# v0_2.net
KiCad netlist of a schematic drawn in EAGLE
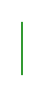
[diagram p0: schematic, sheet 1, part 1 of 2]
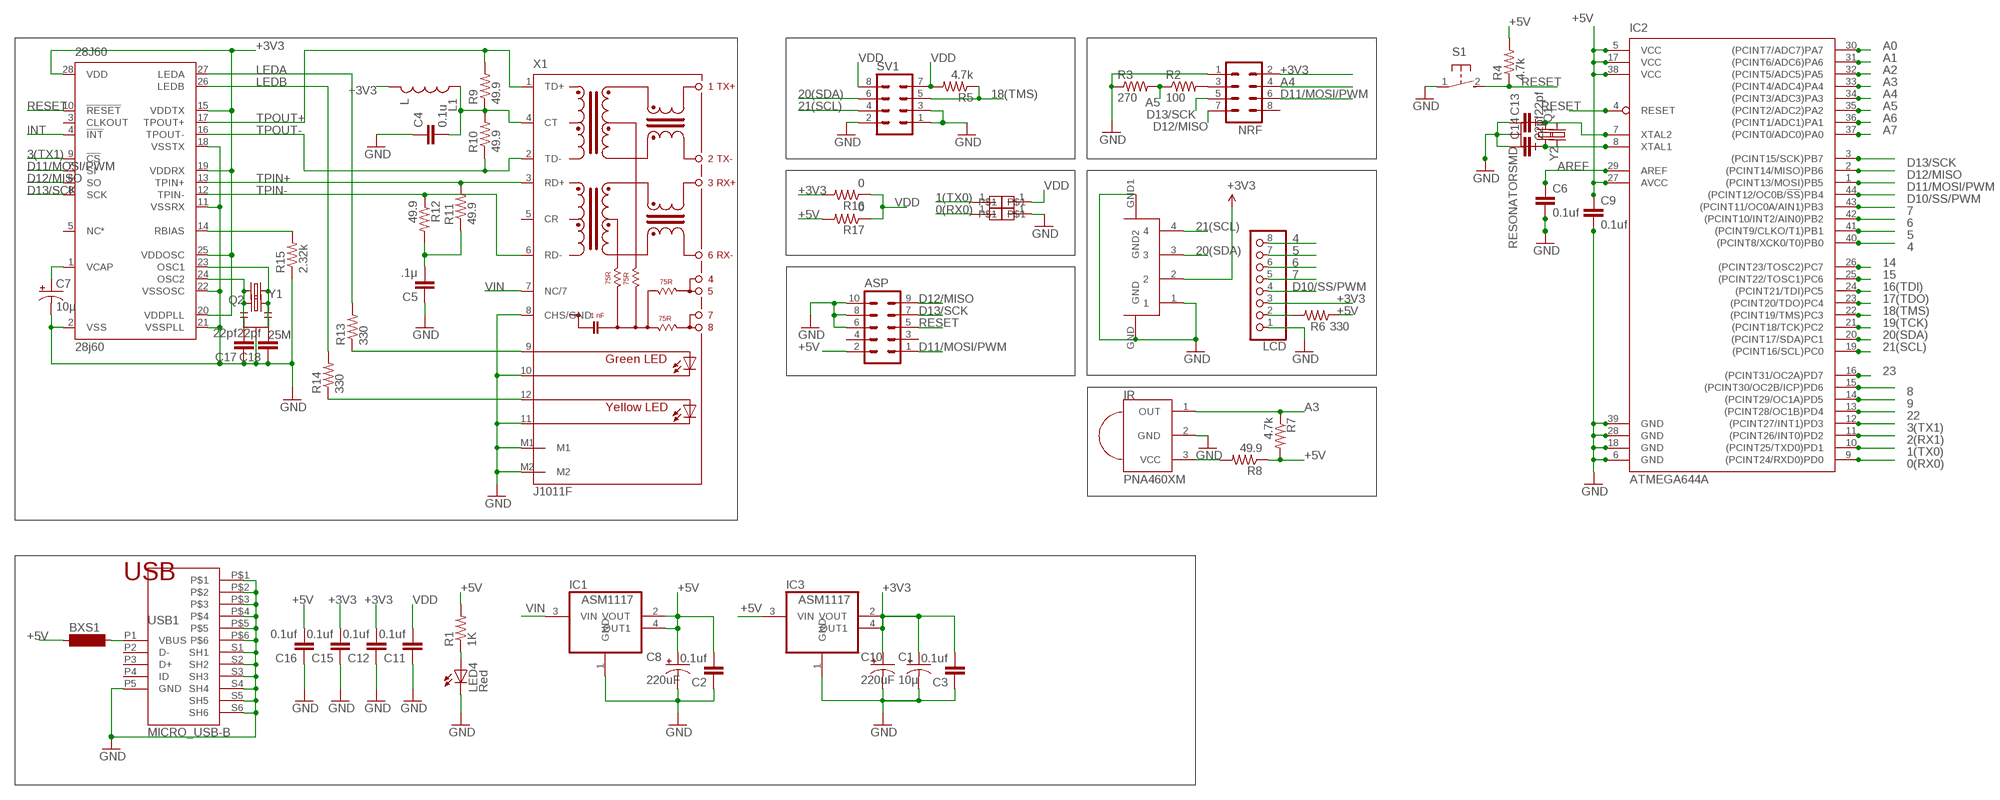
[diagram p1: schematic, sheet 1, part 2 of 2]

(export (version "E")
  (design (tool "Eeschema 10.0.6"))
  (components
    (comp (ref "28J60")
      (value "28j60")
      (footprint "eagle-import:SSOP28DB")
      (libsource (lib "eagle-import") (part "ENC28J60/SS"))
    )
    (comp (ref "ASP")
      (value "MA05-2")
      (footprint "eagle-import:MA05-2")
      (libsource (lib "eagle-import") (part "MA05-2"))
    )
    (comp (ref "BXS1")
      (value "SM-1206")
      (footprint "eagle-import:SM-1206")
      (fields (field (name "OC_FARNELL") "unknown") (field (name "OC_NEWARK") "unknown"))
      (libsource (lib "eagle-import") (part "SM-1206"))
    )
    (comp (ref "C1")
      (value "10μ")
      (footprint "eagle-import:EIA3528")
      (libsource (lib "eagle-import") (part "CAP_POL3528"))
    )
    (comp (ref "C2")
      (value "0.1uf")
      (footprint "eagle-import:0603-CAP")
      (libsource (lib "eagle-import") (part "MY_CAP0603-CAP"))
    )
    (comp (ref "C3")
      (value "0.1uf")
      (footprint "eagle-import:0603-CAP")
      (libsource (lib "eagle-import") (part "MY_CAP0603-CAP"))
    )
    (comp (ref "C4")
      (value "0.1u")
      (footprint "eagle-import:0603-CAP")
      (libsource (lib "eagle-import") (part "CAP0603-CAP"))
    )
    (comp (ref "C5")
      (value ".1μ")
      (footprint "eagle-import:0603-CAP")
      (libsource (lib "eagle-import") (part "CAP0603-CAP"))
    )
    (comp (ref "C6")
      (value "0.1uf")
      (footprint "eagle-import:0603-CAP")
      (libsource (lib "eagle-import") (part "CAP0603-CAP"))
    )
    (comp (ref "C7")
      (value "10μ")
      (footprint "eagle-import:EIA3528")
      (libsource (lib "eagle-import") (part "CAP_POL3528"))
    )
    (comp (ref "C8")
      (value "220uF")
      (footprint "eagle-import:153CLV-0605")
      (libsource (lib "eagle-import") (part "CPOL-US153CLV-0605"))
    )
    (comp (ref "C9")
      (value "0.1uf")
      (footprint "eagle-import:0603-CAP")
      (libsource (lib "eagle-import") (part "CAP0603-CAP"))
    )
    (comp (ref "C10")
      (value "220uF")
      (footprint "eagle-import:153CLV-0605")
      (libsource (lib "eagle-import") (part "CPOL-US153CLV-0605"))
    )
    (comp (ref "C11")
      (value "0.1uf")
      (footprint "eagle-import:0603-CAP")
      (libsource (lib "eagle-import") (part "MY_CAP0603-CAP"))
    )
    (comp (ref "C12")
      (value "0.1uf")
      (footprint "eagle-import:0603-CAP")
      (libsource (lib "eagle-import") (part "MY_CAP0603-CAP"))
    )
    (comp (ref "C13")
      (value "22pf")
      (footprint "eagle-import:0603-CAP")
      (libsource (lib "eagle-import") (part "CAP0603-CAP"))
    )
    (comp (ref "C14")
      (value "22pf")
      (footprint "eagle-import:0603-CAP")
      (libsource (lib "eagle-import") (part "CAP0603-CAP"))
    )
    (comp (ref "C15")
      (value "0.1uf")
      (footprint "eagle-import:0603-CAP")
      (libsource (lib "eagle-import") (part "MY_CAP0603-CAP"))
    )
    (comp (ref "C16")
      (value "0.1uf")
      (footprint "eagle-import:0603-CAP")
      (libsource (lib "eagle-import") (part "MY_CAP0603-CAP"))
    )
    (comp (ref "C17")
      (value "22pf")
      (footprint "eagle-import:0603-CAP")
      (libsource (lib "eagle-import") (part "CAP0603-CAP"))
    )
    (comp (ref "C18")
      (value "22pf")
      (footprint "eagle-import:0603-CAP")
      (libsource (lib "eagle-import") (part "CAP0603-CAP"))
    )
    (comp (ref "IC1")
      (value "ASM1117")
      (footprint "eagle-import:SOT223")
      (fields (field (name "MPN") "REG1117"))
      (libsource (lib "eagle-import") (part "ASM1117"))
    )
    (comp (ref "IC2")
      (value "ATMEGA644A")
      (footprint "eagle-import:TQFP44")
      (fields (field (name "MPN") "ATMEGA644PV-10AU"))
      (libsource (lib "eagle-import") (part "ATMEGA644A"))
    )
    (comp (ref "IC3")
      (value "ASM1117")
      (footprint "eagle-import:SOT223")
      (fields
        (field (name "MPN") "REG1117")
        (field (name "MPN_1") "REG1117")
        (field (name "OC_FARNELL") "1097566")
        (field (name "OC_NEWARK") "14P6981")
      )
      (libsource (lib "eagle-import") (part "ASM1117"))
    )
    (comp (ref "IR")
      (value "PNA460XM")
      (footprint "eagle-import:PNA460XM")
      (libsource (lib "eagle-import") (part "PNA460XM"))
    )
    (comp (ref "L1")
      (value "L")
      (footprint "eagle-import:0603")
      (libsource (lib "eagle-import") (part "INDUCTOR0603"))
    )
    (comp (ref "LCD")
      (value "PINHD-1X8")
      (footprint "eagle-import:1X08")
      (libsource (lib "eagle-import") (part "PINHD-1X8"))
    )
    (comp (ref "LED4")
      (value "Red")
      (footprint "eagle-import:0805-LED")
      (libsource (lib "eagle-import") (part "LED0805"))
    )
    (comp (ref "NRF")
      (value "MA04-2")
      (footprint "eagle-import:MA04-2")
      (libsource (lib "eagle-import") (part "MA04-2"))
    )
    (comp (ref "Q1")
      (value "CRYSTALHC49S")
      (footprint "eagle-import:HC49_S")
      (libsource (lib "eagle-import") (part "CRYSTALHC49S"))
    )
    (comp (ref "Q2")
      (value "CRYSTALHC49S")
      (footprint "eagle-import:HC49_S")
      (fields (field (name "OC_FARNELL") "1667008") (field (name "OC_NEWARK") "unknown"))
      (libsource (lib "eagle-import") (part "CRYSTALHC49S"))
    )
    (comp (ref "R1")
      (value "1K")
      (footprint "eagle-import:0603-RES")
      (libsource (lib "eagle-import") (part "MY_RESISTOR0603-RES"))
    )
    (comp (ref "R2")
      (value "100")
      (footprint "eagle-import:0603-RES")
      (libsource (lib "eagle-import") (part "MY_RESISTOR0603-RES"))
    )
    (comp (ref "R3")
      (value "270")
      (footprint "eagle-import:0603-RES")
      (libsource (lib "eagle-import") (part "MY_RESISTOR0603-RES"))
    )
    (comp (ref "R4")
      (value "4.7k")
      (footprint "eagle-import:0603-RES")
      (libsource (lib "eagle-import") (part "RESISTOR0603-RES"))
    )
    (comp (ref "R5")
      (value "4.7k")
      (footprint "eagle-import:0603-RES")
      (libsource (lib "eagle-import") (part "MY_RESISTOR0603-RES"))
    )
    (comp (ref "R6")
      (value "330")
      (footprint "eagle-import:0603-RES")
      (libsource (lib "eagle-import") (part "MY_RESISTOR0603-RES"))
    )
    (comp (ref "R7")
      (value "4.7k")
      (footprint "eagle-import:0603-RES")
      (libsource (lib "eagle-import") (part "MY_RESISTOR0603-RES"))
    )
    (comp (ref "R8")
      (value "49.9")
      (footprint "eagle-import:0603-RES")
      (libsource (lib "eagle-import") (part "MY_RESISTOR0603-RES"))
    )
    (comp (ref "R9")
      (value "49.9")
      (footprint "eagle-import:0603-RES")
      (libsource (lib "eagle-import") (part "RESISTOR0603-RES"))
    )
    (comp (ref "R10")
      (value "49.9")
      (footprint "eagle-import:0603-RES")
      (libsource (lib "eagle-import") (part "RESISTOR0603-RES"))
    )
    (comp (ref "R11")
      (value "49.9")
      (footprint "eagle-import:0603-RES")
      (libsource (lib "eagle-import") (part "RESISTOR0603-RES"))
    )
    (comp (ref "R12")
      (value "49.9")
      (footprint "eagle-import:0603-RES")
      (libsource (lib "eagle-import") (part "RESISTOR0603-RES"))
    )
    (comp (ref "R13")
      (value "330")
      (footprint "eagle-import:0603-RES")
      (libsource (lib "eagle-import") (part "RESISTOR0603-RES"))
    )
    (comp (ref "R14")
      (value "330")
      (footprint "eagle-import:0603-RES")
      (libsource (lib "eagle-import") (part "RESISTOR0603-RES"))
    )
    (comp (ref "R15")
      (value "2.32k")
      (footprint "eagle-import:0603-RES")
      (libsource (lib "eagle-import") (part "RESISTOR0603-RES"))
    )
    (comp (ref "R16")
      (value "0")
      (footprint "eagle-import:0603-RES")
      (libsource (lib "eagle-import") (part "MY_RESISTOR0603-RES"))
    )
    (comp (ref "R17")
      (value "0")
      (footprint "eagle-import:0603-RES")
      (libsource (lib "eagle-import") (part "MY_RESISTOR0603-RES"))
    )
    (comp (ref "S1")
      (value "31-XX")
      (footprint "eagle-import:B3F-31XX")
      (fields (field (name "MPN") "B3F-3100"))
      (libsource (lib "eagle-import") (part "31-XX"))
    )
    (comp (ref "SV1")
      (value "MA04-2")
      (footprint "eagle-import:MA04-2")
      (libsource (lib "eagle-import") (part "MA04-2"))
    )
    (comp (ref "U$2")
      (value "S4B-XH-SM4-TB")
      (footprint "eagle-import:XH-SM4-TB")
      (libsource (lib "eagle-import") (part "S4B-XH-SM4-TB"))
    )
    (comp (ref "U$4")
      (value "PIN1")
      (footprint "eagle-import:PIN1")
      (libsource (lib "eagle-import") (part "PIN1"))
    )
    (comp (ref "U$5")
      (value "PIN1")
      (footprint "eagle-import:PIN1")
      (libsource (lib "eagle-import") (part "PIN1"))
    )
    (comp (ref "U$6")
      (value "PIN1")
      (footprint "eagle-import:PIN1")
      (libsource (lib "eagle-import") (part "PIN1"))
    )
    (comp (ref "U$7")
      (value "PIN1")
      (footprint "eagle-import:PIN1")
      (libsource (lib "eagle-import") (part "PIN1"))
    )
    (comp (ref "USB1")
      (value "MICRO_USB-B")
      (footprint "eagle-import:USB_MICRO_B")
      (libsource (lib "eagle-import") (part "MICRO_USB-B"))
    )
    (comp (ref "X1")
      (value "J1011F")
      (footprint "eagle-import:HRJ")
      (libsource (lib "eagle-import") (part "RJ45-HR911105A"))
    )
    (comp (ref "Y1")
      (value "25M")
      (footprint "eagle-import:RESONATOR-SMD")
      (libsource (lib "eagle-import") (part "RESONATORSMD"))
    )
    (comp (ref "Y2")
      (value "RESONATORSMD")
      (footprint "eagle-import:RESONATOR-SMD")
      (libsource (lib "eagle-import") (part "MY_RESONATORSMD"))
    )
  )
  (nets
    (net (code "1") (name "+3V3") (class "Default")
      (node (ref "28J60") (pin "15") (pinfunction "VDDTX_15") (pintype "input"))
      (node (ref "28J60") (pin "19") (pinfunction "VDDRX_19") (pintype "input"))
      (node (ref "28J60") (pin "20") (pinfunction "VDDPLL_20") (pintype "input"))
      (node (ref "28J60") (pin "25") (pinfunction "VDDOSC_25") (pintype "input"))
      (node (ref "28J60") (pin "28") (pinfunction "VDD_28") (pintype "input"))
      (node (ref "C1") (pin "A") (pinfunction "+_A") (pintype "passive"))
      (node (ref "C10") (pin "+") (pinfunction "+_+") (pintype "passive"))
      (node (ref "C12") (pin "2") (pinfunction "2_2") (pintype "passive"))
      (node (ref "C15") (pin "2") (pinfunction "2_2") (pintype "passive"))
      (node (ref "C3") (pin "2") (pinfunction "2_2") (pintype "passive"))
      (node (ref "IC3") (pin "2") (pinfunction "VOUT_2") (pintype "output"))
      (node (ref "IC3") (pin "4") (pinfunction "OUT1_4") (pintype "bidirectional"))
      (node (ref "L1") (pin "2") (pinfunction "2_2") (pintype "passive"))
      (node (ref "LCD") (pin "3") (pinfunction "3_3") (pintype "passive"))
      (node (ref "NRF") (pin "2") (pinfunction "2_2") (pintype "passive"))
      (node (ref "R16") (pin "2") (pinfunction "2_2") (pintype "passive"))
      (node (ref "U$2") (pin "2") (pinfunction "2_2") (pintype "bidirectional"))
    )
    (net (code "2") (name "/+5V") (class "Default")
      (node (ref "ASP") (pin "2") (pinfunction "2_2") (pintype "passive"))
      (node (ref "BXS1") (pin "1") (pinfunction "1_1") (pintype "passive"))
      (node (ref "C16") (pin "2") (pinfunction "2_2") (pintype "passive"))
      (node (ref "C2") (pin "2") (pinfunction "2_2") (pintype "passive"))
      (node (ref "C8") (pin "+") (pinfunction "+_+") (pintype "passive"))
      (node (ref "C9") (pin "1") (pinfunction "1_1") (pintype "passive"))
      (node (ref "IC1") (pin "2") (pinfunction "VOUT_2") (pintype "output"))
      (node (ref "IC1") (pin "4") (pinfunction "OUT1_4") (pintype "bidirectional"))
      (node (ref "IC2") (pin "17") (pinfunction "VCC_17") (pintype "power_in"))
      (node (ref "IC2") (pin "27") (pinfunction "AVCC_27") (pintype "power_in"))
      (node (ref "IC2") (pin "38") (pinfunction "VCC_38") (pintype "power_in"))
      (node (ref "IC2") (pin "5") (pinfunction "VCC_5") (pintype "power_in"))
      (node (ref "IC3") (pin "3") (pinfunction "VIN_3") (pintype "input"))
      (node (ref "R1") (pin "2") (pinfunction "2_2") (pintype "passive"))
      (node (ref "R17") (pin "2") (pinfunction "2_2") (pintype "passive"))
      (node (ref "R4") (pin "2") (pinfunction "2_2") (pintype "passive"))
      (node (ref "R6") (pin "1") (pinfunction "1_1") (pintype "passive"))
      (node (ref "R7") (pin "2") (pinfunction "2_2") (pintype "passive"))
      (node (ref "R8") (pin "1") (pinfunction "1_1") (pintype "passive"))
    )
    (net (code "3") (name "/0(RX0)") (class "Default")
      (node (ref "IC2") (pin "9") (pinfunction "(PCINT24/RXD0)PD0_9") (pintype "bidirectional"))
      (node (ref "U$7") (pin "1") (pinfunction "P$1_1") (pintype "bidirectional"))
    )
    (net (code "4") (name "/1(TX0)") (class "Default")
      (node (ref "IC2") (pin "10") (pinfunction "(PCINT25/TXD0)PD1_10") (pintype "bidirectional"))
      (node (ref "U$6") (pin "1") (pinfunction "P$1_1") (pintype "bidirectional"))
    )
    (net (code "5") (name "/2(RX1)") (class "Default")
      (node (ref "IC2") (pin "11") (pinfunction "(PCINT26/INT0)PD2_11") (pintype "bidirectional"))
    )
    (net (code "6") (name "/3(TX1)") (class "Default")
      (node (ref "28J60") (pin "9") (pinfunction "~{CS}_9") (pintype "input"))
      (node (ref "IC2") (pin "12") (pinfunction "(PCINT27/INT1)PD3_12") (pintype "bidirectional"))
    )
    (net (code "7") (name "/4") (class "Default")
      (node (ref "IC2") (pin "40") (pinfunction "(PCINT8/XCK0/T0)PB0_40") (pintype "bidirectional"))
      (node (ref "LCD") (pin "8") (pinfunction "8_8") (pintype "passive"))
    )
    (net (code "8") (name "/5") (class "Default")
      (node (ref "IC2") (pin "41") (pinfunction "(PCINT9/CLKO/T1)PB1_41") (pintype "bidirectional"))
      (node (ref "LCD") (pin "7") (pinfunction "7_7") (pintype "passive"))
    )
    (net (code "9") (name "/6") (class "Default")
      (node (ref "IC2") (pin "42") (pinfunction "(PCINT10/INT2/AIN0)PB2_42") (pintype "bidirectional"))
      (node (ref "LCD") (pin "6") (pinfunction "6_6") (pintype "passive"))
    )
    (net (code "10") (name "/7") (class "Default")
      (node (ref "IC2") (pin "43") (pinfunction "(PCINT11/OC0A/AIN1)PB3_43") (pintype "bidirectional"))
      (node (ref "LCD") (pin "5") (pinfunction "5_5") (pintype "passive"))
    )
    (net (code "11") (name "/8") (class "Default")
      (node (ref "IC2") (pin "15") (pinfunction "(PCINT30/OC2B/ICP)PD6_15") (pintype "bidirectional"))
    )
    (net (code "12") (name "/9") (class "Default")
      (node (ref "IC2") (pin "14") (pinfunction "(PCINT29/OC1A)PD5_14") (pintype "bidirectional"))
    )
    (net (code "13") (name "/14") (class "Default")
      (node (ref "IC2") (pin "26") (pinfunction "(PCINT23/TOSC2)PC7_26") (pintype "output"))
    )
    (net (code "14") (name "/15") (class "Default")
      (node (ref "IC2") (pin "25") (pinfunction "(PCINT22/TOSC1)PC6_25") (pintype "output"))
    )
    (net (code "15") (name "/16(TDI)") (class "Default")
      (node (ref "IC2") (pin "24") (pinfunction "(PCINT21/TDI)PC5_24") (pintype "output"))
    )
    (net (code "16") (name "/17(TDO)") (class "Default")
      (node (ref "IC2") (pin "23") (pinfunction "(PCINT20/TDO)PC4_23") (pintype "output"))
    )
    (net (code "17") (name "/18(TMS)") (class "Default")
      (node (ref "IC2") (pin "22") (pinfunction "(PCINT19/TMS)PC3_22") (pintype "output"))
      (node (ref "R5") (pin "1") (pinfunction "1_1") (pintype "passive"))
      (node (ref "SV1") (pin "5") (pinfunction "5_5") (pintype "passive"))
    )
    (net (code "18") (name "/19(TCK)") (class "Default")
      (node (ref "IC2") (pin "21") (pinfunction "(PCINT18/TCK)PC2_21") (pintype "output"))
    )
    (net (code "19") (name "/20(SDA)") (class "Default")
      (node (ref "IC2") (pin "20") (pinfunction "(PCINT17/SDA)PC1_20") (pintype "output"))
      (node (ref "SV1") (pin "6") (pinfunction "6_6") (pintype "passive"))
      (node (ref "U$2") (pin "3") (pinfunction "3_3") (pintype "bidirectional"))
    )
    (net (code "20") (name "/21(SCL)") (class "Default")
      (node (ref "IC2") (pin "19") (pinfunction "(PCINT16/SCL)PC0_19") (pintype "output"))
      (node (ref "SV1") (pin "4") (pinfunction "4_4") (pintype "passive"))
      (node (ref "U$2") (pin "4") (pinfunction "4_4") (pintype "bidirectional"))
    )
    (net (code "21") (name "/22") (class "Default")
      (node (ref "IC2") (pin "13") (pinfunction "(PCINT28/OC1B)PD4_13") (pintype "bidirectional"))
    )
    (net (code "22") (name "/23") (class "Default")
      (node (ref "IC2") (pin "16") (pinfunction "(PCINT31/OC2A)PD7_16") (pintype "bidirectional"))
    )
    (net (code "23") (name "/A0") (class "Default")
      (node (ref "IC2") (pin "30") (pinfunction "(PCINT7/ADC7)PA7_30") (pintype "bidirectional"))
    )
    (net (code "24") (name "/A1") (class "Default")
      (node (ref "IC2") (pin "31") (pinfunction "(PCINT6/ADC6)PA6_31") (pintype "bidirectional"))
    )
    (net (code "25") (name "/A2") (class "Default")
      (node (ref "IC2") (pin "32") (pinfunction "(PCINT5/ADC5)PA5_32") (pintype "bidirectional"))
    )
    (net (code "26") (name "/A3") (class "Default")
      (node (ref "IC2") (pin "33") (pinfunction "(PCINT4/ADC4)PA4_33") (pintype "bidirectional"))
      (node (ref "IR") (pin "1") (pinfunction "OUT_1") (pintype "output"))
      (node (ref "R7") (pin "1") (pinfunction "1_1") (pintype "passive"))
    )
    (net (code "27") (name "/A4") (class "Default")
      (node (ref "IC2") (pin "34") (pinfunction "(PCINT3/ADC3)PA3_34") (pintype "bidirectional"))
      (node (ref "NRF") (pin "4") (pinfunction "4_4") (pintype "passive"))
    )
    (net (code "28") (name "/A5") (class "Default")
      (node (ref "IC2") (pin "35") (pinfunction "(PCINT2/ADC2)PA2_35") (pintype "bidirectional"))
      (node (ref "R2") (pin "1") (pinfunction "1_1") (pintype "passive"))
      (node (ref "R3") (pin "2") (pinfunction "2_2") (pintype "passive"))
    )
    (net (code "29") (name "/A6") (class "Default")
      (node (ref "IC2") (pin "36") (pinfunction "(PCINT1/ADC1)PA1_36") (pintype "bidirectional"))
    )
    (net (code "30") (name "/A7") (class "Default")
      (node (ref "IC2") (pin "37") (pinfunction "(PCINT0/ADC0)PA0_37") (pintype "bidirectional"))
    )
    (net (code "31") (name "/AREF") (class "Default")
      (node (ref "C6") (pin "1") (pinfunction "1_1") (pintype "passive"))
      (node (ref "IC2") (pin "29") (pinfunction "AREF_29") (pintype "passive"))
    )
    (net (code "32") (name "/D10{slash}SS{slash}PWM") (class "Default")
      (node (ref "IC2") (pin "44") (pinfunction "(PCINT12/OC0B/~{SS})PB4_44") (pintype "bidirectional"))
      (node (ref "LCD") (pin "4") (pinfunction "4_4") (pintype "passive"))
    )
    (net (code "33") (name "/D11{slash}MOSI{slash}PWM") (class "Default")
      (node (ref "28J60") (pin "7") (pinfunction "SI_7") (pintype "input"))
      (node (ref "ASP") (pin "1") (pinfunction "1_1") (pintype "passive"))
      (node (ref "IC2") (pin "1") (pinfunction "(PCINT13/MOSI)PB5_1") (pintype "bidirectional"))
      (node (ref "NRF") (pin "6") (pinfunction "6_6") (pintype "passive"))
    )
    (net (code "34") (name "/D12{slash}MISO") (class "Default")
      (node (ref "28J60") (pin "6") (pinfunction "SO_6") (pintype "output"))
      (node (ref "ASP") (pin "9") (pinfunction "9_9") (pintype "passive"))
      (node (ref "IC2") (pin "2") (pinfunction "(PCINT14/MISO)PB6_2") (pintype "bidirectional"))
      (node (ref "NRF") (pin "7") (pinfunction "7_7") (pintype "passive"))
    )
    (net (code "35") (name "/D13{slash}SCK") (class "Default")
      (node (ref "28J60") (pin "8") (pinfunction "SCK_8") (pintype "input"))
      (node (ref "ASP") (pin "7") (pinfunction "7_7") (pintype "passive"))
      (node (ref "IC2") (pin "3") (pinfunction "(PCINT15/SCK)PB7_3") (pintype "bidirectional"))
      (node (ref "NRF") (pin "5") (pinfunction "5_5") (pintype "passive"))
    )
    (net (code "36") (name "/INT") (class "Default")
      (node (ref "28J60") (pin "4") (pinfunction "~{INT}_4") (pintype "output"))
    )
    (net (code "37") (name "/LEDA") (class "Default")
      (node (ref "28J60") (pin "27") (pinfunction "LEDA_27") (pintype "output"))
      (node (ref "R13") (pin "2") (pinfunction "2_2") (pintype "passive"))
    )
    (net (code "38") (name "/LEDB") (class "Default")
      (node (ref "28J60") (pin "26") (pinfunction "LEDB_26") (pintype "output"))
      (node (ref "R14") (pin "2") (pinfunction "2_2") (pintype "passive"))
    )
    (net (code "39") (name "/RESET") (class "Default")
      (node (ref "28J60") (pin "10") (pinfunction "~{RESET}_10") (pintype "input"))
      (node (ref "ASP") (pin "5") (pinfunction "5_5") (pintype "passive"))
      (node (ref "IC2") (pin "4") (pinfunction "RESET_4") (pintype "input"))
      (node (ref "R4") (pin "1") (pinfunction "1_1") (pintype "passive"))
      (node (ref "S1") (pin "2") (pinfunction "S_2") (pintype "passive"))
    )
    (net (code "40") (name "/TPIN+") (class "Default")
      (node (ref "28J60") (pin "13") (pinfunction "TPIN+_13") (pintype "input"))
      (node (ref "R11") (pin "2") (pinfunction "2_2") (pintype "passive"))
      (node (ref "X1") (pin "3") (pinfunction "RD+_3") (pintype "input"))
    )
    (net (code "41") (name "/TPIN-") (class "Default")
      (node (ref "28J60") (pin "12") (pinfunction "TPIN-_12") (pintype "input"))
      (node (ref "R12") (pin "1") (pinfunction "1_1") (pintype "passive"))
      (node (ref "X1") (pin "6") (pinfunction "RD-_6") (pintype "input"))
    )
    (net (code "42") (name "/TPOUT+") (class "Default")
      (node (ref "28J60") (pin "17") (pinfunction "TPOUT+_17") (pintype "output"))
      (node (ref "R9") (pin "2") (pinfunction "2_2") (pintype "passive"))
      (node (ref "X1") (pin "1") (pinfunction "TD+_1") (pintype "input"))
    )
    (net (code "43") (name "/TPOUT-") (class "Default")
      (node (ref "28J60") (pin "16") (pinfunction "TPOUT-_16") (pintype "output"))
      (node (ref "R10") (pin "1") (pinfunction "1_1") (pintype "passive"))
      (node (ref "X1") (pin "2") (pinfunction "TD-_2") (pintype "input"))
    )
    (net (code "44") (name "/VDD") (class "Default")
      (node (ref "C11") (pin "2") (pinfunction "2_2") (pintype "passive"))
      (node (ref "R16") (pin "1") (pinfunction "1_1") (pintype "passive"))
      (node (ref "R17") (pin "1") (pinfunction "1_1") (pintype "passive"))
      (node (ref "R5") (pin "2") (pinfunction "2_2") (pintype "passive"))
      (node (ref "SV1") (pin "7") (pinfunction "7_7") (pintype "passive"))
      (node (ref "SV1") (pin "8") (pinfunction "8_8") (pintype "passive"))
      (node (ref "U$5") (pin "1") (pinfunction "P$1_1") (pintype "bidirectional"))
    )
    (net (code "45") (name "/VIN") (class "Default")
      (node (ref "IC1") (pin "3") (pinfunction "VIN_3") (pintype "input"))
      (node (ref "X1") (pin "7") (pinfunction "NC/7_7") (pintype "input"))
    )
    (net (code "46") (name "GND") (class "Default")
      (node (ref "28J60") (pin "11") (pinfunction "VSSRX_11") (pintype "input"))
      (node (ref "28J60") (pin "18") (pinfunction "VSSTX_18") (pintype "input"))
      (node (ref "28J60") (pin "2") (pinfunction "VSS_2") (pintype "input"))
      (node (ref "28J60") (pin "21") (pinfunction "VSSPLL_21") (pintype "input"))
      (node (ref "28J60") (pin "22") (pinfunction "VSSOSC_22") (pintype "input"))
      (node (ref "ASP") (pin "10") (pinfunction "10_10") (pintype "passive"))
      (node (ref "ASP") (pin "6") (pinfunction "6_6") (pintype "passive"))
      (node (ref "ASP") (pin "8") (pinfunction "8_8") (pintype "passive"))
      (node (ref "C1") (pin "C") (pinfunction "-_C") (pintype "passive"))
      (node (ref "C10") (pin "-") (pinfunction "-_-") (pintype "passive"))
      (node (ref "C11") (pin "1") (pinfunction "1_1") (pintype "passive"))
      (node (ref "C12") (pin "1") (pinfunction "1_1") (pintype "passive"))
      (node (ref "C13") (pin "1") (pinfunction "1_1") (pintype "passive"))
      (node (ref "C14") (pin "1") (pinfunction "1_1") (pintype "passive"))
      (node (ref "C15") (pin "1") (pinfunction "1_1") (pintype "passive"))
      (node (ref "C16") (pin "1") (pinfunction "1_1") (pintype "passive"))
      (node (ref "C17") (pin "1") (pinfunction "1_1") (pintype "passive"))
      (node (ref "C18") (pin "1") (pinfunction "1_1") (pintype "passive"))
      (node (ref "C2") (pin "1") (pinfunction "1_1") (pintype "passive"))
      (node (ref "C3") (pin "1") (pinfunction "1_1") (pintype "passive"))
      (node (ref "C4") (pin "1") (pinfunction "1_1") (pintype "passive"))
      (node (ref "C5") (pin "1") (pinfunction "1_1") (pintype "passive"))
      (node (ref "C6") (pin "2") (pinfunction "2_2") (pintype "passive"))
      (node (ref "C7") (pin "C") (pinfunction "-_C") (pintype "passive"))
      (node (ref "C8") (pin "-") (pinfunction "-_-") (pintype "passive"))
      (node (ref "C9") (pin "2") (pinfunction "2_2") (pintype "passive"))
      (node (ref "IC1") (pin "1") (pinfunction "GND_1") (pintype "power_in"))
      (node (ref "IC2") (pin "18") (pinfunction "GND_18") (pintype "power_in"))
      (node (ref "IC2") (pin "28") (pinfunction "GND_28") (pintype "power_in"))
      (node (ref "IC2") (pin "39") (pinfunction "GND_39") (pintype "power_in"))
      (node (ref "IC2") (pin "6") (pinfunction "GND_6") (pintype "power_in"))
      (node (ref "IC3") (pin "1") (pinfunction "GND_1") (pintype "power_in"))
      (node (ref "IR") (pin "2") (pinfunction "GND_2") (pintype "power_in"))
      (node (ref "LCD") (pin "1") (pinfunction "1_1") (pintype "passive"))
      (node (ref "LED4") (pin "C") (pinfunction "C_C") (pintype "passive"))
      (node (ref "NRF") (pin "1") (pinfunction "1_1") (pintype "passive"))
      (node (ref "R15") (pin "1") (pinfunction "1_1") (pintype "passive"))
      (node (ref "R3") (pin "1") (pinfunction "1_1") (pintype "passive"))
      (node (ref "S1") (pin "1") (pinfunction "P_1") (pintype "passive"))
      (node (ref "SV1") (pin "1") (pinfunction "1_1") (pintype "passive"))
      (node (ref "SV1") (pin "2") (pinfunction "2_2") (pintype "passive"))
      (node (ref "SV1") (pin "3") (pinfunction "3_3") (pintype "passive"))
      (node (ref "U$2") (pin "1") (pinfunction "1_1") (pintype "bidirectional"))
      (node (ref "U$2") (pin "GND") (pinfunction "GND_GND") (pintype "bidirectional"))
      (node (ref "U$2") (pin "GND1") (pinfunction "GND2_GND1") (pintype "bidirectional"))
      (node (ref "U$4") (pin "1") (pinfunction "P$1_1") (pintype "bidirectional"))
      (node (ref "USB1") (pin "P$1") (pinfunction "P$1_P$1") (pintype "bidirectional"))
      (node (ref "USB1") (pin "P$2") (pinfunction "P$2_P$2") (pintype "bidirectional"))
      (node (ref "USB1") (pin "P$3") (pinfunction "P$3_P$3") (pintype "bidirectional"))
      (node (ref "USB1") (pin "P$4") (pinfunction "P$4_P$4") (pintype "bidirectional"))
      (node (ref "USB1") (pin "P$5") (pinfunction "P$5_P$5") (pintype "bidirectional"))
      (node (ref "USB1") (pin "P$6") (pinfunction "P$6_P$6") (pintype "bidirectional"))
      (node (ref "USB1") (pin "P5") (pinfunction "GND_P5") (pintype "passive"))
      (node (ref "USB1") (pin "S1") (pinfunction "SH1_S1") (pintype "passive"))
      (node (ref "USB1") (pin "S2") (pinfunction "SH2_S2") (pintype "passive"))
      (node (ref "USB1") (pin "S3") (pinfunction "SH3_S3") (pintype "passive"))
      (node (ref "USB1") (pin "S4") (pinfunction "SH4_S4") (pintype "passive"))
      (node (ref "USB1") (pin "S5") (pinfunction "SH5_S5") (pintype "passive"))
      (node (ref "USB1") (pin "S6") (pinfunction "SH6_S6") (pintype "passive"))
      (node (ref "X1") (pin "10") (pinfunction "C-R_10") (pintype "passive"))
      (node (ref "X1") (pin "11") (pinfunction "C-L_11") (pintype "passive"))
      (node (ref "X1") (pin "8") (pinfunction "CHS/GND_8") (pintype "input"))
      (node (ref "X1") (pin "M1") (pinfunction "M1_M1") (pintype "bidirectional"))
      (node (ref "X1") (pin "M2") (pinfunction "M2_M2") (pintype "bidirectional"))
      (node (ref "Y1") (pin "2") (pinfunction "2_2") (pintype "passive"))
      (node (ref "Y2") (pin "2") (pinfunction "2_2") (pintype "passive"))
    )
    (net (code "47") (name "Net-(28J60-OSC1)") (class "Default")
      (node (ref "28J60") (pin "23") (pinfunction "OSC1_23") (pintype "input"))
      (node (ref "C18") (pin "2") (pinfunction "2_2") (pintype "passive"))
      (node (ref "Q2") (pin "1") (pinfunction "1_1") (pintype "passive"))
      (node (ref "Y1") (pin "3") (pinfunction "3_3") (pintype "passive"))
    )
    (net (code "48") (name "Net-(28J60-OSC2)") (class "Default")
      (node (ref "28J60") (pin "24") (pinfunction "OSC2_24") (pintype "output"))
      (node (ref "C17") (pin "2") (pinfunction "2_2") (pintype "passive"))
      (node (ref "Q2") (pin "2") (pinfunction "2_2") (pintype "passive"))
      (node (ref "Y1") (pin "1") (pinfunction "1_1") (pintype "passive"))
    )
    (net (code "49") (name "Net-(28J60-RBIAS)") (class "Default")
      (node (ref "28J60") (pin "14") (pinfunction "RBIAS_14") (pintype "input"))
      (node (ref "R15") (pin "2") (pinfunction "2_2") (pintype "passive"))
    )
    (net (code "50") (name "Net-(28J60-VCAP)") (class "Default")
      (node (ref "28J60") (pin "1") (pinfunction "VCAP_1") (pintype "input"))
      (node (ref "C7") (pin "A") (pinfunction "+_A") (pintype "passive"))
    )
    (net (code "51") (name "Net-(C5-Pad2)") (class "Default")
      (node (ref "C5") (pin "2") (pinfunction "2_2") (pintype "passive"))
      (node (ref "R11") (pin "1") (pinfunction "1_1") (pintype "passive"))
      (node (ref "R12") (pin "2") (pinfunction "2_2") (pintype "passive"))
    )
    (net (code "52") (name "Net-(IC2-XTAL1)") (class "Default")
      (node (ref "C14") (pin "2") (pinfunction "2_2") (pintype "passive"))
      (node (ref "IC2") (pin "8") (pinfunction "XTAL1_8") (pintype "bidirectional"))
      (node (ref "Q1") (pin "1") (pinfunction "1_1") (pintype "passive"))
      (node (ref "Y2") (pin "3") (pinfunction "3_3") (pintype "passive"))
    )
    (net (code "53") (name "Net-(IC2-XTAL2)") (class "Default")
      (node (ref "C13") (pin "2") (pinfunction "2_2") (pintype "passive"))
      (node (ref "IC2") (pin "7") (pinfunction "XTAL2_7") (pintype "bidirectional"))
      (node (ref "Q1") (pin "2") (pinfunction "2_2") (pintype "passive"))
      (node (ref "Y2") (pin "1") (pinfunction "1_1") (pintype "passive"))
    )
    (net (code "54") (name "Net-(IR-VCC)") (class "Default")
      (node (ref "IR") (pin "3") (pinfunction "VCC_3") (pintype "power_in"))
      (node (ref "R8") (pin "2") (pinfunction "2_2") (pintype "passive"))
    )
    (net (code "55") (name "Net-(LCD-Pad2)") (class "Default")
      (node (ref "LCD") (pin "2") (pinfunction "2_2") (pintype "passive"))
      (node (ref "R6") (pin "2") (pinfunction "2_2") (pintype "passive"))
    )
    (net (code "56") (name "Net-(LED4-PadA)") (class "Default")
      (node (ref "LED4") (pin "A") (pinfunction "A_A") (pintype "passive"))
      (node (ref "R1") (pin "1") (pinfunction "1_1") (pintype "passive"))
    )
    (net (code "57") (name "Net-(NRF-Pad3)") (class "Default")
      (node (ref "NRF") (pin "3") (pinfunction "3_3") (pintype "passive"))
      (node (ref "R2") (pin "2") (pinfunction "2_2") (pintype "passive"))
    )
    (net (code "58") (name "Net-(USB1-VBUS)") (class "Default")
      (node (ref "BXS1") (pin "2") (pinfunction "2_2") (pintype "passive"))
      (node (ref "USB1") (pin "P1") (pinfunction "VBUS_P1") (pintype "power_in"))
    )
    (net (code "59") (name "Net-(X1-A-R)") (class "Default")
      (node (ref "R13") (pin "1") (pinfunction "1_1") (pintype "passive"))
      (node (ref "X1") (pin "9") (pinfunction "A-R_9") (pintype "passive"))
    )
    (net (code "60") (name "Net-(X1-AL)") (class "Default")
      (node (ref "R14") (pin "1") (pinfunction "1_1") (pintype "passive"))
      (node (ref "X1") (pin "12") (pinfunction "AL_12") (pintype "passive"))
    )
    (net (code "61") (name "Net-(X1-CT)") (class "Default")
      (node (ref "C4") (pin "2") (pinfunction "2_2") (pintype "passive"))
      (node (ref "L1") (pin "1") (pinfunction "1_1") (pintype "passive"))
      (node (ref "R10") (pin "2") (pinfunction "2_2") (pintype "passive"))
      (node (ref "R9") (pin "1") (pinfunction "1_1") (pintype "passive"))
      (node (ref "X1") (pin "4") (pinfunction "CT_4") (pintype "input"))
    )
    (net (code "62") (name "unconnected-(28J60-CLKOUT-Pad3)") (class "Default")
      (node (ref "28J60") (pin "3") (pinfunction "CLKOUT_3") (pintype "output"))
    )
    (net (code "63") (name "unconnected-(28J60-NC*-Pad5)") (class "Default")
      (node (ref "28J60") (pin "5") (pinfunction "NC*_5") (pintype "output"))
    )
    (net (code "64") (name "unconnected-(ASP-Pad3)") (class "Default")
      (node (ref "ASP") (pin "3") (pinfunction "3_3") (pintype "passive"))
    )
    (net (code "65") (name "unconnected-(ASP-Pad4)") (class "Default")
      (node (ref "ASP") (pin "4") (pinfunction "4_4") (pintype "passive"))
    )
    (net (code "66") (name "unconnected-(NRF-Pad8)") (class "Default")
      (node (ref "NRF") (pin "8") (pinfunction "8_8") (pintype "passive"))
    )
    (net (code "67") (name "unconnected-(USB1-D+-PadP3)") (class "Default")
      (node (ref "USB1") (pin "P3") (pinfunction "D+_P3") (pintype "bidirectional"))
    )
    (net (code "68") (name "unconnected-(USB1-D--PadP2)") (class "Default")
      (node (ref "USB1") (pin "P2") (pinfunction "D-_P2") (pintype "bidirectional"))
    )
    (net (code "69") (name "unconnected-(USB1-ID-PadP4)") (class "Default")
      (node (ref "USB1") (pin "P4") (pinfunction "ID_P4") (pintype "bidirectional"))
    )
    (net (code "70") (name "unconnected-(X1-CR-Pad5)") (class "Default")
      (node (ref "X1") (pin "5") (pinfunction "CR_5") (pintype "input"))
    )
  )
)
